# 23138_adapter_passive.net
KiCad netlist of a schematic drawn in EAGLE
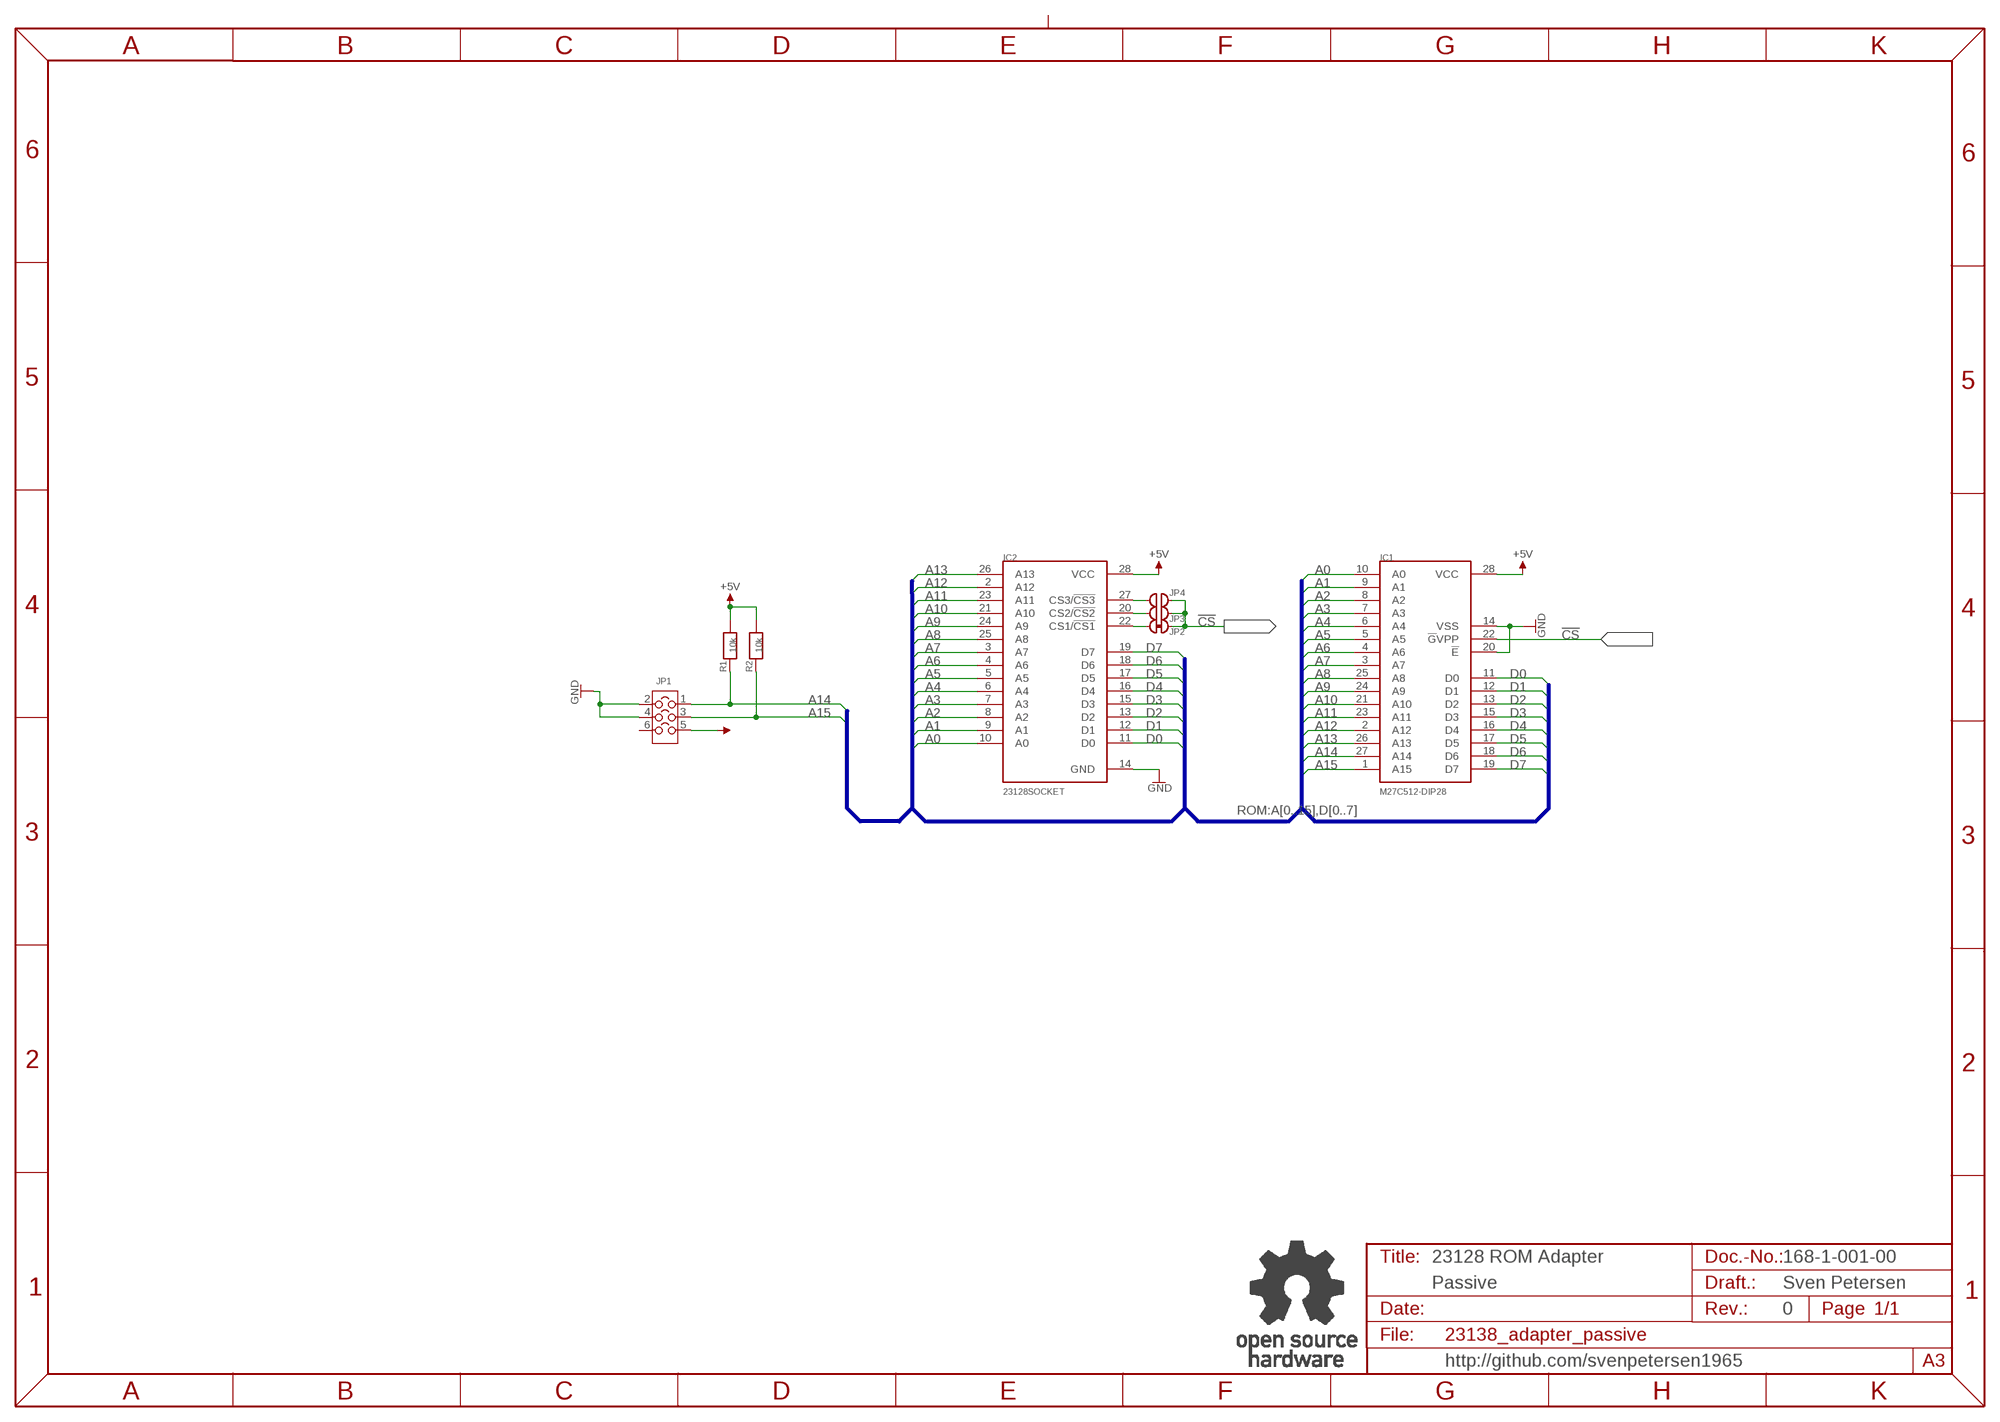
[diagram p0: schematic, sheet 1]

(export (version "E")
  (design (tool "Eeschema 10.0.6"))
  (components
    (comp (ref "IC1")
      (value "M27C512-DIP28")
      (footprint "eagle-import:DIL28-6")
      (libsource (lib "eagle-import") (part "M27C512-DIP28"))
    )
    (comp (ref "IC2")
      (value "23128SOCKET")
      (footprint "eagle-import:DIL28_SOCKET")
      (libsource (lib "eagle-import") (part "23128SOCKET"))
    )
    (comp (ref "JP1")
      (value "COMBI-3X2P-90°")
      (footprint "eagle-import:COMBI-3X2W")
      (libsource (lib "eagle-import") (part "COMBI-3X2P-90°"))
    )
    (comp (ref "JP2")
      (value "CLOSED")
      (footprint "eagle-import:CP_CL")
      (libsource (lib "eagle-import") (part "CLOSED"))
    )
    (comp (ref "JP3")
      (value "OPEN")
      (footprint "eagle-import:CP_OP")
      (libsource (lib "eagle-import") (part "OPEN"))
    )
    (comp (ref "JP4")
      (value "OPEN")
      (footprint "eagle-import:CP_OP")
      (libsource (lib "eagle-import") (part "OPEN"))
    )
    (comp (ref "R1")
      (value "10k")
      (footprint "eagle-import:0805")
      (libsource (lib "eagle-import") (part "R-0805"))
    )
    (comp (ref "R2")
      (value "10k")
      (footprint "eagle-import:0805")
      (libsource (lib "eagle-import") (part "R-0805"))
    )
    (comp (ref "U$21")
      (value "OPEN_SOURCE_HW")
      (footprint "eagle-import:OPENHW")
      (libsource (lib "eagle-import") (part "OPEN_SOURCE_HW"))
    )
  )
  (nets
    (net (code "1") (name "+5V") (class "Default")
      (node (ref "IC1") (pin "28") (pinfunction "VCC_28") (pintype "power_in"))
      (node (ref "IC2") (pin "28") (pinfunction "VCC_28") (pintype "power_in"))
      (node (ref "JP1") (pin "5") (pinfunction "5_5") (pintype "bidirectional"))
      (node (ref "R1") (pin "2") (pinfunction "2_2") (pintype "passive"))
      (node (ref "R2") (pin "2") (pinfunction "2_2") (pintype "passive"))
    )
    (net (code "2") (name "/A0") (class "Default")
      (node (ref "IC1") (pin "10") (pinfunction "A0_10") (pintype "input"))
      (node (ref "IC2") (pin "10") (pinfunction "A0_10") (pintype "input"))
    )
    (net (code "3") (name "/A1") (class "Default")
      (node (ref "IC1") (pin "9") (pinfunction "A1_9") (pintype "input"))
      (node (ref "IC2") (pin "9") (pinfunction "A1_9") (pintype "input"))
    )
    (net (code "4") (name "/A2") (class "Default")
      (node (ref "IC1") (pin "8") (pinfunction "A2_8") (pintype "input"))
      (node (ref "IC2") (pin "8") (pinfunction "A2_8") (pintype "input"))
    )
    (net (code "5") (name "/A3") (class "Default")
      (node (ref "IC1") (pin "7") (pinfunction "A3_7") (pintype "input"))
      (node (ref "IC2") (pin "7") (pinfunction "A3_7") (pintype "input"))
    )
    (net (code "6") (name "/A4") (class "Default")
      (node (ref "IC1") (pin "6") (pinfunction "A4_6") (pintype "input"))
      (node (ref "IC2") (pin "6") (pinfunction "A4_6") (pintype "input"))
    )
    (net (code "7") (name "/A5") (class "Default")
      (node (ref "IC1") (pin "5") (pinfunction "A5_5") (pintype "input"))
      (node (ref "IC2") (pin "5") (pinfunction "A5_5") (pintype "input"))
    )
    (net (code "8") (name "/A6") (class "Default")
      (node (ref "IC1") (pin "4") (pinfunction "A6_4") (pintype "input"))
      (node (ref "IC2") (pin "4") (pinfunction "A6_4") (pintype "input"))
    )
    (net (code "9") (name "/A7") (class "Default")
      (node (ref "IC1") (pin "3") (pinfunction "A7_3") (pintype "input"))
      (node (ref "IC2") (pin "3") (pinfunction "A7_3") (pintype "input"))
    )
    (net (code "10") (name "/A8") (class "Default")
      (node (ref "IC1") (pin "25") (pinfunction "A8_25") (pintype "input"))
      (node (ref "IC2") (pin "25") (pinfunction "A8_25") (pintype "input"))
    )
    (net (code "11") (name "/A9") (class "Default")
      (node (ref "IC1") (pin "24") (pinfunction "A9_24") (pintype "input"))
      (node (ref "IC2") (pin "24") (pinfunction "A9_24") (pintype "input"))
    )
    (net (code "12") (name "/A10") (class "Default")
      (node (ref "IC1") (pin "21") (pinfunction "A10_21") (pintype "input"))
      (node (ref "IC2") (pin "21") (pinfunction "A10_21") (pintype "input"))
    )
    (net (code "13") (name "/A11") (class "Default")
      (node (ref "IC1") (pin "23") (pinfunction "A11_23") (pintype "input"))
      (node (ref "IC2") (pin "23") (pinfunction "A11_23") (pintype "input"))
    )
    (net (code "14") (name "/A12") (class "Default")
      (node (ref "IC1") (pin "2") (pinfunction "A12_2") (pintype "input"))
      (node (ref "IC2") (pin "2") (pinfunction "A12_2") (pintype "input"))
    )
    (net (code "15") (name "/A13") (class "Default")
      (node (ref "IC1") (pin "26") (pinfunction "A13_26") (pintype "input"))
      (node (ref "IC2") (pin "26") (pinfunction "A13_26") (pintype "input"))
    )
    (net (code "16") (name "/A14") (class "Default")
      (node (ref "IC1") (pin "27") (pinfunction "A14_27") (pintype "input"))
      (node (ref "JP1") (pin "1") (pinfunction "1_1") (pintype "bidirectional"))
      (node (ref "R1") (pin "1") (pinfunction "1_1") (pintype "passive"))
    )
    (net (code "17") (name "/A15") (class "Default")
      (node (ref "IC1") (pin "1") (pinfunction "A15_1") (pintype "input"))
      (node (ref "JP1") (pin "3") (pinfunction "3_3") (pintype "bidirectional"))
      (node (ref "R2") (pin "1") (pinfunction "1_1") (pintype "passive"))
    )
    (net (code "18") (name "/D0") (class "Default")
      (node (ref "IC1") (pin "11") (pinfunction "D0_11") (pintype "bidirectional"))
      (node (ref "IC2") (pin "11") (pinfunction "D0_11") (pintype "tri_state"))
    )
    (net (code "19") (name "/D1") (class "Default")
      (node (ref "IC1") (pin "12") (pinfunction "D1_12") (pintype "bidirectional"))
      (node (ref "IC2") (pin "12") (pinfunction "D1_12") (pintype "tri_state"))
    )
    (net (code "20") (name "/D2") (class "Default")
      (node (ref "IC1") (pin "13") (pinfunction "D2_13") (pintype "bidirectional"))
      (node (ref "IC2") (pin "13") (pinfunction "D2_13") (pintype "tri_state"))
    )
    (net (code "21") (name "/D3") (class "Default")
      (node (ref "IC1") (pin "15") (pinfunction "D3_15") (pintype "bidirectional"))
      (node (ref "IC2") (pin "15") (pinfunction "D3_15") (pintype "tri_state"))
    )
    (net (code "22") (name "/D4") (class "Default")
      (node (ref "IC1") (pin "16") (pinfunction "D4_16") (pintype "bidirectional"))
      (node (ref "IC2") (pin "16") (pinfunction "D4_16") (pintype "tri_state"))
    )
    (net (code "23") (name "/D5") (class "Default")
      (node (ref "IC1") (pin "17") (pinfunction "D5_17") (pintype "bidirectional"))
      (node (ref "IC2") (pin "17") (pinfunction "D5_17") (pintype "tri_state"))
    )
    (net (code "24") (name "/D6") (class "Default")
      (node (ref "IC1") (pin "18") (pinfunction "D6_18") (pintype "bidirectional"))
      (node (ref "IC2") (pin "18") (pinfunction "D6_18") (pintype "tri_state"))
    )
    (net (code "25") (name "/D7") (class "Default")
      (node (ref "IC1") (pin "19") (pinfunction "D7_19") (pintype "bidirectional"))
      (node (ref "IC2") (pin "19") (pinfunction "D7_19") (pintype "tri_state"))
    )
    (net (code "27") (name "/~{CS}") (class "Default")
      (node (ref "IC1") (pin "22") (pinfunction "~{G}VPP_22") (pintype "input"))
      (node (ref "JP2") (pin "2") (pinfunction "2_2") (pintype "passive"))
      (node (ref "JP3") (pin "2") (pinfunction "2_2") (pintype "passive"))
      (node (ref "JP4") (pin "2") (pinfunction "2_2") (pintype "passive"))
    )
    (net (code "28") (name "GND") (class "Default")
      (node (ref "IC1") (pin "14") (pinfunction "VSS_14") (pintype "power_in"))
      (node (ref "IC1") (pin "20") (pinfunction "~{E}_20") (pintype "input"))
      (node (ref "IC2") (pin "14") (pinfunction "GND_14") (pintype "power_in"))
      (node (ref "JP1") (pin "2") (pinfunction "2_2") (pintype "bidirectional"))
      (node (ref "JP1") (pin "4") (pinfunction "4_4") (pintype "bidirectional"))
    )
    (net (code "29") (name "Net-(IC2-CS1{slash}~{CS1})") (class "Default")
      (node (ref "IC2") (pin "22") (pinfunction "CS1/~{CS1}_22") (pintype "input"))
      (node (ref "JP2") (pin "1") (pinfunction "1_1") (pintype "passive"))
    )
    (net (code "30") (name "Net-(IC2-CS2{slash}~{CS2})") (class "Default")
      (node (ref "IC2") (pin "20") (pinfunction "CS2/~{CS2}_20") (pintype "input"))
      (node (ref "JP3") (pin "1") (pinfunction "1_1") (pintype "passive"))
    )
    (net (code "31") (name "Net-(IC2-CS3{slash}~{CS3})") (class "Default")
      (node (ref "IC2") (pin "27") (pinfunction "CS3/~{CS3}_27") (pintype "input"))
      (node (ref "JP4") (pin "1") (pinfunction "1_1") (pintype "passive"))
    )
    (net (code "32") (name "unconnected-(JP1-Pad6)") (class "Default")
      (node (ref "JP1") (pin "6") (pinfunction "6_6") (pintype "bidirectional"))
    )
  )
)
